# NanoDapAdapter.net
KiCad netlist of a schematic drawn in EAGLE
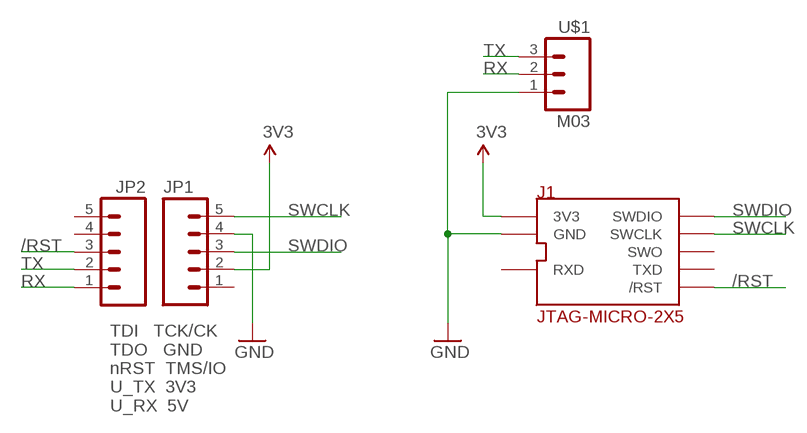
[diagram p0: schematic, sheet 1]

(export (version "E")
  (design (tool "Eeschema 10.0.6"))
  (components
    (comp (ref "J1")
      (value "JTAG-MICRO-2X5")
      (footprint "eagle-import:JTAG-MICRO-2X5")
      (libsource (lib "eagle-import") (part "JTAG-MICRO-2X5"))
    )
    (comp (ref "JP1")
      (value "M05PTH")
      (footprint "eagle-import:1X05")
      (libsource (lib "eagle-import") (part "M05PTH"))
    )
    (comp (ref "JP2")
      (value "M05PTH")
      (footprint "eagle-import:1X05")
      (libsource (lib "eagle-import") (part "M05PTH"))
    )
    (comp (ref "U$1")
      (value "M03")
      (footprint "eagle-import:1X03")
      (libsource (lib "eagle-import") (part "M03"))
    )
  )
  (nets
    (net (code "1") (name "/RX") (class "Default")
      (node (ref "JP2") (pin "1") (pinfunction "1_1") (pintype "passive"))
      (node (ref "U$1") (pin "2") (pinfunction "2_2") (pintype "passive"))
    )
    (net (code "2") (name "/SWCLK") (class "Default")
      (node (ref "J1") (pin "4") (pinfunction "SWCLK_4") (pintype "passive"))
      (node (ref "JP1") (pin "5") (pinfunction "5_5") (pintype "passive"))
    )
    (net (code "3") (name "/SWDIO") (class "Default")
      (node (ref "J1") (pin "2") (pinfunction "SWDIO_2") (pintype "passive"))
      (node (ref "JP1") (pin "3") (pinfunction "3_3") (pintype "passive"))
    )
    (net (code "4") (name "/TX") (class "Default")
      (node (ref "JP2") (pin "2") (pinfunction "2_2") (pintype "passive"))
      (node (ref "U$1") (pin "3") (pinfunction "3_3") (pintype "passive"))
    )
    (net (code "5") (name "/{slash}RST") (class "Default")
      (node (ref "J1") (pin "10") (pinfunction "/RST_10") (pintype "passive"))
      (node (ref "JP2") (pin "3") (pinfunction "3_3") (pintype "passive"))
    )
    (net (code "6") (name "3V3") (class "Default")
      (node (ref "J1") (pin "1") (pinfunction "3V3_1") (pintype "passive"))
      (node (ref "JP1") (pin "2") (pinfunction "2_2") (pintype "passive"))
    )
    (net (code "7") (name "GND") (class "Default")
      (node (ref "J1") (pin "3") (pinfunction "GND_3") (pintype "passive"))
      (node (ref "J1") (pin "5") (pinfunction "GND_5") (pintype "passive"))
      (node (ref "J1") (pin "9") (pinfunction "GND_9") (pintype "passive"))
      (node (ref "JP1") (pin "4") (pinfunction "4_4") (pintype "passive"))
      (node (ref "U$1") (pin "1") (pinfunction "1_1") (pintype "passive"))
    )
    (net (code "8") (name "unconnected-(J1-RXD-Pad7)") (class "Default")
      (node (ref "J1") (pin "7") (pinfunction "RXD_7") (pintype "passive"))
    )
    (net (code "9") (name "unconnected-(J1-SWO-Pad6)") (class "Default")
      (node (ref "J1") (pin "6") (pinfunction "SWO_6") (pintype "passive"))
    )
    (net (code "10") (name "unconnected-(J1-TXD-Pad8)") (class "Default")
      (node (ref "J1") (pin "8") (pinfunction "TXD_8") (pintype "passive"))
    )
    (net (code "11") (name "unconnected-(JP1-Pad1)") (class "Default")
      (node (ref "JP1") (pin "1") (pinfunction "1_1") (pintype "passive"))
    )
    (net (code "12") (name "unconnected-(JP2-Pad4)") (class "Default")
      (node (ref "JP2") (pin "4") (pinfunction "4_4") (pintype "passive"))
    )
    (net (code "13") (name "unconnected-(JP2-Pad5)") (class "Default")
      (node (ref "JP2") (pin "5") (pinfunction "5_5") (pintype "passive"))
    )
  )
)
